# 5V_12V_Logic.net
KiCad netlist of a schematic drawn in Altium Designer
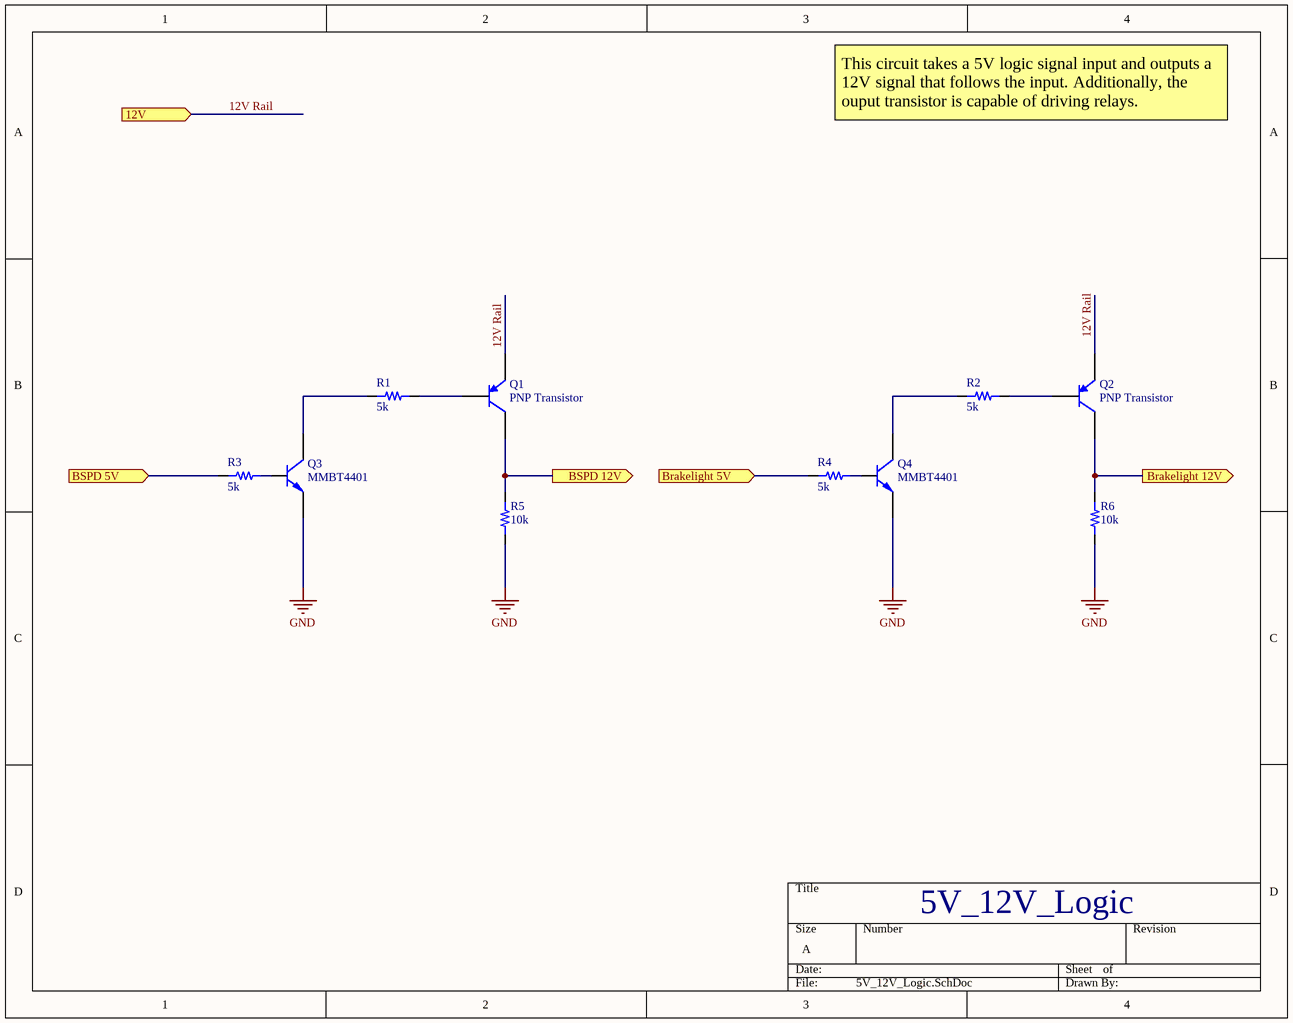
[diagram p0: 5V_12V_Logic.SchDoc]

(export (version "E")
  (design (tool "Eeschema 10.0.6"))
  (components
    (comp (ref "Q1")
      (value "PNP Transistor")
      (footprint "SOT23-3")
      (description "Bipolar (BJT) Transistor PNP 25V 1.5A 100MHz")
      (fields (field (name "POWER") "625") (field (name "CREATEDBY") "Kevin"))
      (libsource (lib "altlib") (part "PNP Transistor"))
    )
    (comp (ref "Q2")
      (value "PNP Transistor")
      (footprint "SOT23-3")
      (description "Bipolar (BJT) Transistor PNP 25V 1.5A 100MHz")
      (fields (field (name "POWER") "625") (field (name "CREATEDBY") "Kevin"))
      (libsource (lib "altlib") (part "PNP Transistor"))
    )
    (comp (ref "Q3") (value "MMBT4401") (footprint "SOT23-3") (libsource (lib "altlib") (part "MMBT4401")))
    (comp (ref "Q4") (value "MMBT4401") (footprint "SOT23-3") (libsource (lib "altlib") (part "MMBT4401")))
    (comp (ref "R1")
      (value "resistor")
      (footprint "RES 0603/1608")
      (fields (field (name "RESISTANCE") "5k"))
      (libsource (lib "altlib") (part "resistor"))
    )
    (comp (ref "R2")
      (value "resistor")
      (footprint "RES 0603/1608")
      (fields (field (name "RESISTANCE") "5k"))
      (libsource (lib "altlib") (part "resistor"))
    )
    (comp (ref "R3")
      (value "resistor")
      (footprint "RES 0603/1608")
      (fields (field (name "RESISTANCE") "5k"))
      (libsource (lib "altlib") (part "resistor"))
    )
    (comp (ref "R4")
      (value "resistor")
      (footprint "RES 0603/1608")
      (fields (field (name "RESISTANCE") "5k"))
      (libsource (lib "altlib") (part "resistor"))
    )
    (comp (ref "R5")
      (value "resistor")
      (footprint "RES 0603/1608")
      (fields (field (name "RESISTANCE") "10k"))
      (libsource (lib "altlib") (part "resistor"))
    )
    (comp (ref "R6")
      (value "resistor")
      (footprint "RES 0603/1608")
      (fields (field (name "RESISTANCE") "10k"))
      (libsource (lib "altlib") (part "resistor"))
    )
  )
  (nets
    (net (code "1") (name "/12V Rail") (class "Default")
      (node (ref "Q1") (pin "2") (pinfunction "E_2") (pintype "passive"))
      (node (ref "Q2") (pin "2") (pinfunction "E_2") (pintype "passive"))
    )
    (net (code "2") (name "/BSPD 5V") (class "Default")
      (node (ref "R3") (pin "1") (pinfunction "1_1") (pintype "passive"))
    )
    (net (code "3") (name "/BSPD 12V") (class "Default")
      (node (ref "Q1") (pin "3") (pinfunction "C_3") (pintype "passive"))
      (node (ref "R5") (pin "2") (pinfunction "2_2") (pintype "passive"))
    )
    (net (code "4") (name "/Brakelight 5V") (class "Default")
      (node (ref "R4") (pin "1") (pinfunction "1_1") (pintype "passive"))
    )
    (net (code "5") (name "/Brakelight 12V") (class "Default")
      (node (ref "Q2") (pin "3") (pinfunction "C_3") (pintype "passive"))
      (node (ref "R6") (pin "2") (pinfunction "2_2") (pintype "passive"))
    )
    (net (code "6") (name "GND") (class "Default")
      (node (ref "Q3") (pin "2") (pinfunction "E_2") (pintype "passive"))
      (node (ref "Q4") (pin "2") (pinfunction "E_2") (pintype "passive"))
      (node (ref "R5") (pin "1") (pinfunction "1_1") (pintype "passive"))
      (node (ref "R6") (pin "1") (pinfunction "1_1") (pintype "passive"))
    )
    (net (code "7") (name "Net-(Q1-B)") (class "Default")
      (node (ref "Q1") (pin "1") (pinfunction "B_1") (pintype "passive"))
      (node (ref "R1") (pin "2") (pinfunction "2_2") (pintype "passive"))
    )
    (net (code "8") (name "Net-(Q2-B)") (class "Default")
      (node (ref "Q2") (pin "1") (pinfunction "B_1") (pintype "passive"))
      (node (ref "R2") (pin "2") (pinfunction "2_2") (pintype "passive"))
    )
    (net (code "9") (name "Net-(Q3-B)") (class "Default")
      (node (ref "Q3") (pin "1") (pinfunction "B_1") (pintype "passive"))
      (node (ref "R3") (pin "2") (pinfunction "2_2") (pintype "passive"))
    )
    (net (code "10") (name "Net-(Q3-C)") (class "Default")
      (node (ref "Q3") (pin "3") (pinfunction "C_3") (pintype "passive"))
      (node (ref "R1") (pin "1") (pinfunction "1_1") (pintype "passive"))
    )
    (net (code "11") (name "Net-(Q4-B)") (class "Default")
      (node (ref "Q4") (pin "1") (pinfunction "B_1") (pintype "passive"))
      (node (ref "R4") (pin "2") (pinfunction "2_2") (pintype "passive"))
    )
    (net (code "12") (name "Net-(Q4-C)") (class "Default")
      (node (ref "Q4") (pin "3") (pinfunction "C_3") (pintype "passive"))
      (node (ref "R2") (pin "1") (pinfunction "1_1") (pintype "passive"))
    )
  )
)
